# CoProcessor.net
KiCad netlist of a schematic drawn in Altium Designer
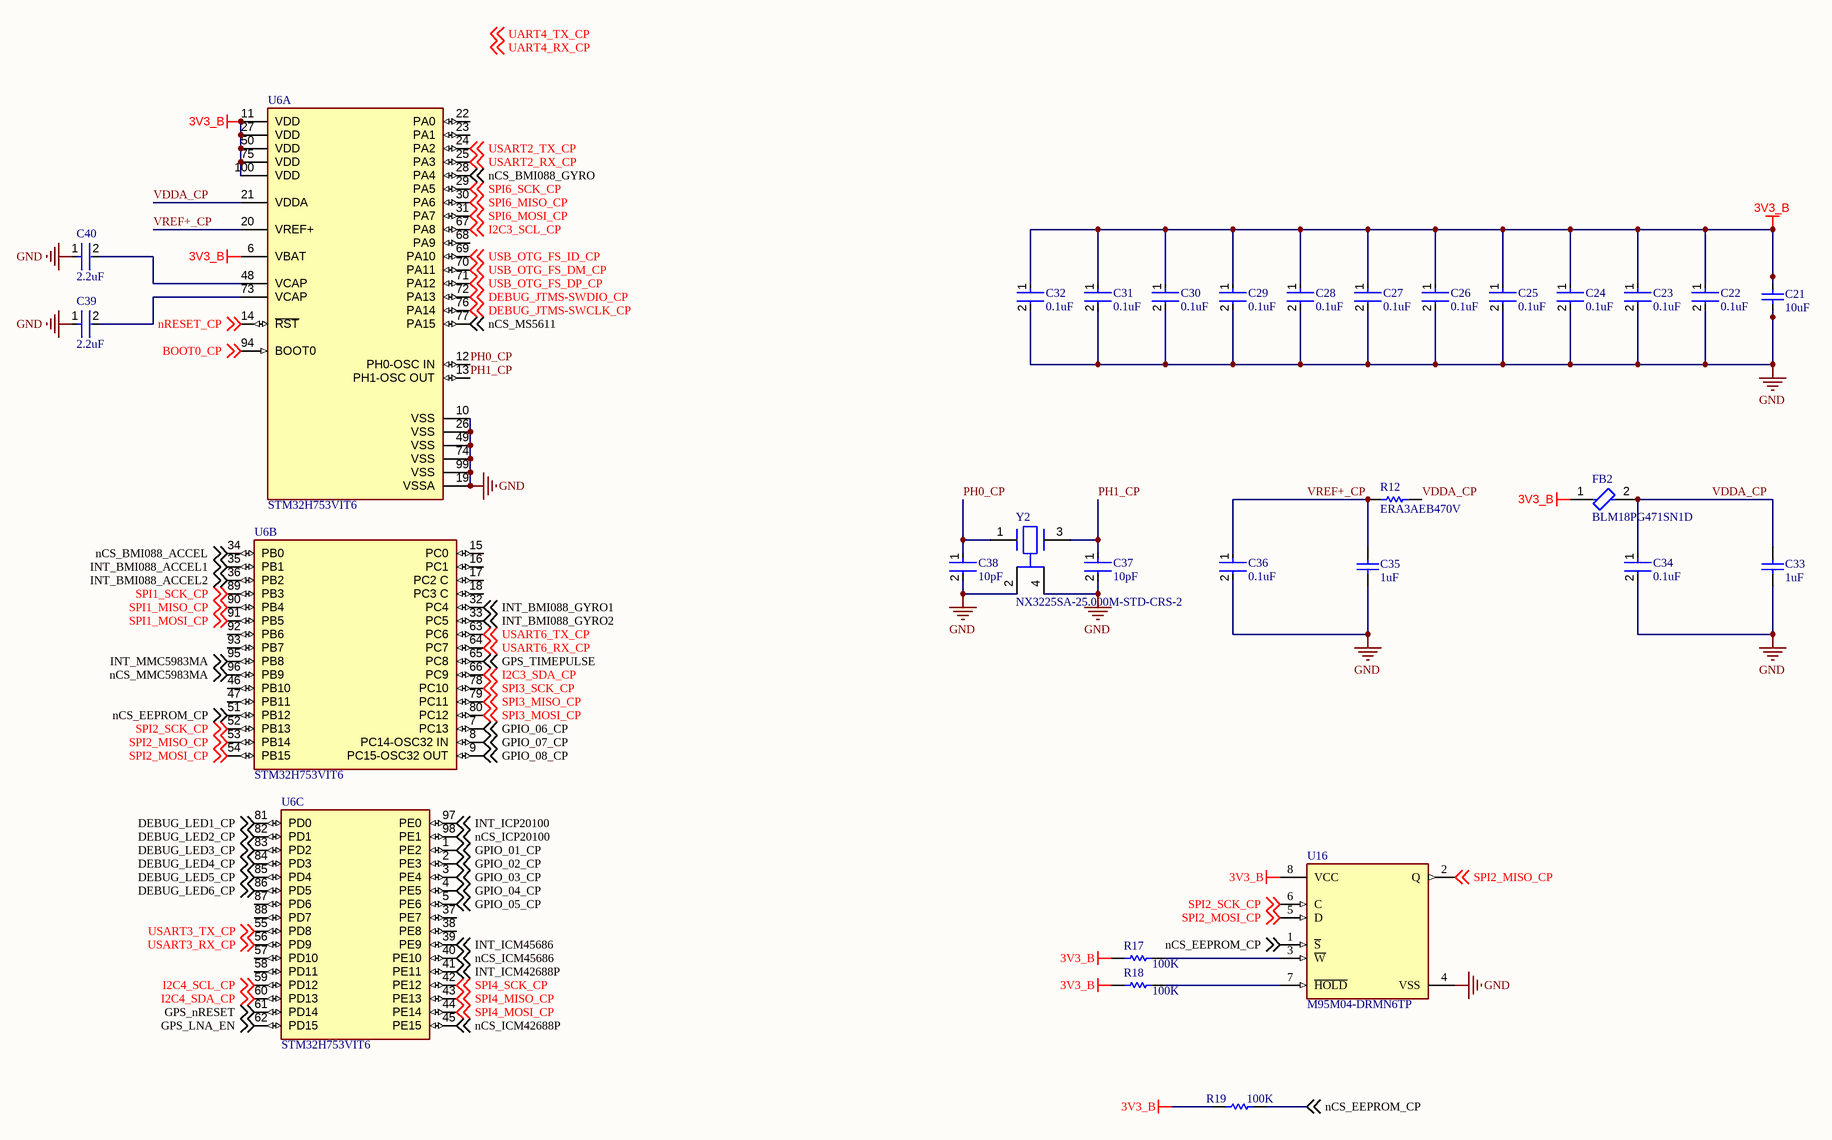
[diagram p0: CoProcessor.SchDoc]

(export (version "E")
  (design (tool "Eeschema 10.0.6"))
  (components
    (comp (ref "C21")
      (value "10uF")
      (footprint "CAPC2013X145X50LL20T25")
      (fields (field (name "MANUFACTURER") "Kemet") (field (name "PART NUMBER") "C0805C106K8RACTU"))
      (libsource (lib "Altium Content Vault") (part "CAP"))
    )
    (comp (ref "C22")
      (value "0.1uF")
      (footprint "FP-C0603C-CF-MFG")
      (description "CAP CER 0.1UF 50V X7R 0603")
      (fields (field (name "TOLERANCE") "0.1") (field (name "MANUFACTURER") "KEMET"))
      (libsource (lib "Altium Content Vault") (part "b4654b650e69147ec39a6b967a45e02"))
    )
    (comp (ref "C23")
      (value "0.1uF")
      (footprint "FP-C0603C-CF-MFG")
      (description "CAP CER 0.1UF 50V X7R 0603")
      (fields (field (name "TOLERANCE") "0.1") (field (name "MANUFACTURER") "KEMET"))
      (libsource (lib "Altium Content Vault") (part "b4654b650e69147ec39a6b967a45e02"))
    )
    (comp (ref "C24")
      (value "0.1uF")
      (footprint "FP-C0603C-CF-MFG")
      (description "CAP CER 0.1UF 50V X7R 0603")
      (fields (field (name "TOLERANCE") "0.1") (field (name "MANUFACTURER") "KEMET"))
      (libsource (lib "Altium Content Vault") (part "b4654b650e69147ec39a6b967a45e02"))
    )
    (comp (ref "C25")
      (value "0.1uF")
      (footprint "FP-C0603C-CF-MFG")
      (description "CAP CER 0.1UF 50V X7R 0603")
      (fields (field (name "TOLERANCE") "0.1") (field (name "MANUFACTURER") "KEMET"))
      (libsource (lib "Altium Content Vault") (part "b4654b650e69147ec39a6b967a45e02"))
    )
    (comp (ref "C26")
      (value "0.1uF")
      (footprint "FP-C0603C-CF-MFG")
      (description "CAP CER 0.1UF 50V X7R 0603")
      (fields (field (name "TOLERANCE") "0.1") (field (name "MANUFACTURER") "KEMET"))
      (libsource (lib "Altium Content Vault") (part "b4654b650e69147ec39a6b967a45e02"))
    )
    (comp (ref "C27")
      (value "0.1uF")
      (footprint "FP-C0603C-CF-MFG")
      (description "CAP CER 0.1UF 50V X7R 0603")
      (fields (field (name "TOLERANCE") "0.1") (field (name "MANUFACTURER") "KEMET"))
      (libsource (lib "Altium Content Vault") (part "b4654b650e69147ec39a6b967a45e02"))
    )
    (comp (ref "C28")
      (value "0.1uF")
      (footprint "FP-C0603C-CF-MFG")
      (description "CAP CER 0.1UF 50V X7R 0603")
      (fields (field (name "TOLERANCE") "0.1") (field (name "MANUFACTURER") "KEMET"))
      (libsource (lib "Altium Content Vault") (part "b4654b650e69147ec39a6b967a45e02"))
    )
    (comp (ref "C29")
      (value "0.1uF")
      (footprint "FP-C0603C-CF-MFG")
      (description "CAP CER 0.1UF 50V X7R 0603")
      (fields (field (name "TOLERANCE") "0.1") (field (name "MANUFACTURER") "KEMET"))
      (libsource (lib "Altium Content Vault") (part "b4654b650e69147ec39a6b967a45e02"))
    )
    (comp (ref "C30")
      (value "0.1uF")
      (footprint "FP-C0603C-CF-MFG")
      (description "CAP CER 0.1UF 50V X7R 0603")
      (fields (field (name "TOLERANCE") "0.1") (field (name "MANUFACTURER") "KEMET"))
      (libsource (lib "Altium Content Vault") (part "b4654b650e69147ec39a6b967a45e02"))
    )
    (comp (ref "C31")
      (value "0.1uF")
      (footprint "FP-C0603C-CF-MFG")
      (description "CAP CER 0.1UF 50V X7R 0603")
      (fields (field (name "TOLERANCE") "0.1") (field (name "MANUFACTURER") "KEMET"))
      (libsource (lib "Altium Content Vault") (part "b4654b650e69147ec39a6b967a45e02"))
    )
    (comp (ref "C32")
      (value "0.1uF")
      (footprint "FP-C0603C-CF-MFG")
      (description "CAP CER 0.1UF 50V X7R 0603")
      (fields (field (name "TOLERANCE") "0.1") (field (name "MANUFACTURER") "KEMET"))
      (libsource (lib "Altium Content Vault") (part "b4654b650e69147ec39a6b967a45e02"))
    )
    (comp (ref "C33")
      (value "1uF")
      (footprint "CAPC1608X90X35LL15T15")
      (fields (field (name "MANUFACTURER") "Kemet") (field (name "PART NUMBER") "C0603C105K4RACTU"))
      (libsource (lib "Altium Content Vault") (part "CAP"))
    )
    (comp (ref "C34")
      (value "0.1uF")
      (footprint "FP-C0603C-CF-MFG")
      (description "CAP CER 0.1UF 50V X7R 0603")
      (fields (field (name "TOLERANCE") "0.1") (field (name "MANUFACTURER") "KEMET"))
      (libsource (lib "Altium Content Vault") (part "b4654b650e69147ec39a6b967a45e02"))
    )
    (comp (ref "C35")
      (value "1uF")
      (footprint "CAPC1608X90X35LL15T15")
      (fields (field (name "MANUFACTURER") "Kemet") (field (name "PART NUMBER") "C0603C105K4RACTU"))
      (libsource (lib "Altium Content Vault") (part "CAP"))
    )
    (comp (ref "C36")
      (value "0.1uF")
      (footprint "FP-C0603C-CF-MFG")
      (description "CAP CER 0.1UF 50V X7R 0603")
      (fields (field (name "TOLERANCE") "0.1") (field (name "MANUFACTURER") "KEMET"))
      (libsource (lib "Altium Content Vault") (part "b4654b650e69147ec39a6b967a45e02"))
    )
    (comp (ref "C37")
      (value "10pF")
      (footprint "FP-C0603C-CF-MFG")
      (description "CAP CER 10PF 50V NP0 0603")
      (fields (field (name "MANUFACTURER") "KEMET") (field (name "TOLERANCE") "0.25 pF"))
      (libsource (lib "Altium Content Vault") (part "b4654b650e69147ec39a6b967a45e02"))
    )
    (comp (ref "C38")
      (value "10pF")
      (footprint "FP-C0603C-CF-MFG")
      (description "CAP CER 10PF 50V NP0 0603")
      (fields (field (name "MANUFACTURER") "KEMET") (field (name "TOLERANCE") "0.25 pF"))
      (libsource (lib "Altium Content Vault") (part "b4654b650e69147ec39a6b967a45e02"))
    )
    (comp (ref "C39")
      (value "2.2uF")
      (footprint "FP-GRM188-0_1-e0_2_0_5-MFG")
      (description "Chip Multilayer Ceramic Capacitors for General Purpose, 0603, 2.2uF, X7R, 15%, 10%, 10V")
      (fields (field (name "VOLTAGE") "10V") (field (name "TOLERANCE") "10%"))
      (libsource (lib "Altium Content Vault") (part "11868f565c42a9108669ba33697ecf6"))
    )
    (comp (ref "C40")
      (value "2.2uF")
      (footprint "FP-GRM188-0_1-e0_2_0_5-MFG")
      (description "Chip Multilayer Ceramic Capacitors for General Purpose, 0603, 2.2uF, X7R, 15%, 10%, 10V")
      (fields (field (name "VOLTAGE") "10V") (field (name "TOLERANCE") "10%"))
      (libsource (lib "Altium Content Vault") (part "11868f565c42a9108669ba33697ecf6"))
    )
    (comp (ref "FB2")
      (value "BLM18PG471SN1D")
      (footprint "FP-BLM18-0_15-t0_8-MFG")
      (description "Chip Ferrite Bead, 0603, 470Ω @ 100MHz, 0.2Ω, 25%, 1A")
      (fields (field (name "TOLERANCE") "25%"))
      (libsource (lib "Altium Content Vault") (part "5f30dd21d616792df468990f7003faa"))
    )
    (comp (ref "R12")
      (value "ERA3AEB470V")
      (footprint "RESC1608X55X30NL20T20")
      (fields (field (name "MANUFACTURER") "Panasonic"))
      (libsource (lib "Altium Content Vault") (part "RES"))
    )
    (comp (ref "R17")
      (value "100K")
      (footprint "RESC1608X55X30ML20T10")
      (fields (field (name "PART NUMBER") "RK73B1JTTD104J") (field (name "MANUFACTURER") "KOA Speer"))
      (libsource (lib "Altium Content Vault") (part "RES"))
    )
    (comp (ref "R18")
      (value "100K")
      (footprint "RESC1608X55X30ML20T10")
      (fields (field (name "PART NUMBER") "RK73B1JTTD104J") (field (name "MANUFACTURER") "KOA Speer"))
      (libsource (lib "Altium Content Vault") (part "RES"))
    )
    (comp (ref "R19")
      (value "100K")
      (footprint "RESC1608X55X30ML20T10")
      (fields (field (name "PART NUMBER") "RK73B1JTTD104J") (field (name "MANUFACTURER") "KOA Speer"))
      (libsource (lib "Altium Content Vault") (part "RES"))
    )
    (comp (ref "U6")
      (value "STM32H753VIT6")
      (footprint "FP-LQFP100-1L-MFG")
      (description "LQFP 100 14X14X1.4")
      (fields
        (field (name "OCTOPART") "https://octopart.com/stm32h753vit6-stmicroelectronics-87879769")
        (field (name "MANUFACTURER") "STMicroelectronics")
      )
      (libsource (lib "Altium Content Vault") (part "0d804454ec25a714beb1806164230ed"))
    )
    (comp (ref "U16")
      (value "M95M04-DRMN6TP")
      (footprint "FP-SO8N-SO-A-IPC_C")
      (description "STANDARD SERIAL EEPROM")
      (libsource (lib "Altium Content Vault") (part "c55af301368cfa6937ebbf8cb00c05d"))
    )
    (comp (ref "Y2")
      (value "NX3225SA-25.000M-STD-CRS-2")
      (footprint "FP-NX3225SA-MFG")
      (description "CRYSTAL 25.0000MHZ 8PF SMD")
      (fields
        (field (name "OCTOPART") "https://octopart.com/nx3225sa-25.000m-std-crs-2-ndk-51374293")
        (field (name "MANUFACTURER") "NDK")
      )
      (libsource (lib "Altium Content Vault") (part "2e6e5a9c86ccbddb5e6335a7c0ff6ff"))
    )
  )
  (nets
    (net (code "1") (name "/PH0_CP") (class "Default")
      (node (ref "C38") (pin "1") (pinfunction "1_1") (pintype "passive"))
      (node (ref "U6") (pin "12") (pinfunction "PH0-OSC_IN_12") (pintype "bidirectional"))
      (node (ref "Y2") (pin "1") (pinfunction "1_1") (pintype "passive"))
    )
    (net (code "2") (name "/PH1_CP") (class "Default")
      (node (ref "C37") (pin "1") (pinfunction "1_1") (pintype "passive"))
      (node (ref "U6") (pin "13") (pinfunction "PH1-OSC_OUT_13") (pintype "bidirectional"))
      (node (ref "Y2") (pin "3") (pinfunction "3_3") (pintype "passive"))
    )
    (net (code "3") (name "/VDDA_CP") (class "Default")
      (node (ref "C33") (pin "1") (pinfunction "1_1") (pintype "passive"))
      (node (ref "C34") (pin "1") (pinfunction "1_1") (pintype "passive"))
      (node (ref "FB2") (pin "2") (pinfunction "2_2") (pintype "passive"))
      (node (ref "R12") (pin "2") (pinfunction "2_2") (pintype "passive"))
      (node (ref "U6") (pin "21") (pinfunction "VDDA_21") (pintype "power_in"))
    )
    (net (code "4") (name "/VREF+_CP") (class "Default")
      (node (ref "C35") (pin "1") (pinfunction "1_1") (pintype "passive"))
      (node (ref "C36") (pin "1") (pinfunction "1_1") (pintype "passive"))
      (node (ref "R12") (pin "1") (pinfunction "1_1") (pintype "passive"))
      (node (ref "U6") (pin "20") (pinfunction "VREF+_20") (pintype "power_in"))
    )
    (net (code "5") (name "3V3_B") (class "Default")
      (node (ref "C21") (pin "1") (pinfunction "1_1") (pintype "passive"))
      (node (ref "C22") (pin "1") (pinfunction "1_1") (pintype "passive"))
      (node (ref "C23") (pin "1") (pinfunction "1_1") (pintype "passive"))
      (node (ref "C24") (pin "1") (pinfunction "1_1") (pintype "passive"))
      (node (ref "C25") (pin "1") (pinfunction "1_1") (pintype "passive"))
      (node (ref "C26") (pin "1") (pinfunction "1_1") (pintype "passive"))
      (node (ref "C27") (pin "1") (pinfunction "1_1") (pintype "passive"))
      (node (ref "C28") (pin "1") (pinfunction "1_1") (pintype "passive"))
      (node (ref "C29") (pin "1") (pinfunction "1_1") (pintype "passive"))
      (node (ref "C30") (pin "1") (pinfunction "1_1") (pintype "passive"))
      (node (ref "C31") (pin "1") (pinfunction "1_1") (pintype "passive"))
      (node (ref "C32") (pin "1") (pinfunction "1_1") (pintype "passive"))
      (node (ref "FB2") (pin "1") (pinfunction "1_1") (pintype "passive"))
      (node (ref "R17") (pin "2") (pinfunction "2_2") (pintype "passive"))
      (node (ref "R18") (pin "2") (pinfunction "2_2") (pintype "passive"))
      (node (ref "R19") (pin "2") (pinfunction "2_2") (pintype "passive"))
      (node (ref "U16") (pin "8") (pinfunction "VCC_8") (pintype "power_in"))
      (node (ref "U6") (pin "100") (pinfunction "VDD_100") (pintype "power_in"))
      (node (ref "U6") (pin "11") (pinfunction "VDD_11") (pintype "power_in"))
      (node (ref "U6") (pin "27") (pinfunction "VDD_27") (pintype "power_in"))
      (node (ref "U6") (pin "50") (pinfunction "VDD_50") (pintype "power_in"))
      (node (ref "U6") (pin "6") (pinfunction "VBAT_6") (pintype "power_in"))
      (node (ref "U6") (pin "75") (pinfunction "VDD_75") (pintype "power_in"))
    )
    (net (code "6") (name "BOOT0_CP") (class "Default")
      (node (ref "U6") (pin "94") (pinfunction "BOOT0_94") (pintype "input"))
    )
    (net (code "7") (name "DEBUG_JTMS-SWCLK_CP") (class "Default")
      (node (ref "U6") (pin "76") (pinfunction "PA14_76") (pintype "bidirectional"))
    )
    (net (code "8") (name "DEBUG_JTMS-SWDIO_CP") (class "Default")
      (node (ref "U6") (pin "72") (pinfunction "PA13_72") (pintype "bidirectional"))
    )
    (net (code "9") (name "DEBUG_LED1_CP") (class "Default")
      (node (ref "U6") (pin "81") (pinfunction "PD0_81") (pintype "bidirectional"))
    )
    (net (code "10") (name "DEBUG_LED2_CP") (class "Default")
      (node (ref "U6") (pin "82") (pinfunction "PD1_82") (pintype "bidirectional"))
    )
    (net (code "11") (name "DEBUG_LED3_CP") (class "Default")
      (node (ref "U6") (pin "83") (pinfunction "PD2_83") (pintype "bidirectional"))
    )
    (net (code "12") (name "DEBUG_LED4_CP") (class "Default")
      (node (ref "U6") (pin "84") (pinfunction "PD3_84") (pintype "bidirectional"))
    )
    (net (code "13") (name "DEBUG_LED5_CP") (class "Default")
      (node (ref "U6") (pin "85") (pinfunction "PD4_85") (pintype "bidirectional"))
    )
    (net (code "14") (name "DEBUG_LED6_CP") (class "Default")
      (node (ref "U6") (pin "86") (pinfunction "PD5_86") (pintype "bidirectional"))
    )
    (net (code "15") (name "GND") (class "Default")
      (node (ref "C21") (pin "2") (pinfunction "2_2") (pintype "passive"))
      (node (ref "C22") (pin "2") (pinfunction "2_2") (pintype "passive"))
      (node (ref "C23") (pin "2") (pinfunction "2_2") (pintype "passive"))
      (node (ref "C24") (pin "2") (pinfunction "2_2") (pintype "passive"))
      (node (ref "C25") (pin "2") (pinfunction "2_2") (pintype "passive"))
      (node (ref "C26") (pin "2") (pinfunction "2_2") (pintype "passive"))
      (node (ref "C27") (pin "2") (pinfunction "2_2") (pintype "passive"))
      (node (ref "C28") (pin "2") (pinfunction "2_2") (pintype "passive"))
      (node (ref "C29") (pin "2") (pinfunction "2_2") (pintype "passive"))
      (node (ref "C30") (pin "2") (pinfunction "2_2") (pintype "passive"))
      (node (ref "C31") (pin "2") (pinfunction "2_2") (pintype "passive"))
      (node (ref "C32") (pin "2") (pinfunction "2_2") (pintype "passive"))
      (node (ref "C33") (pin "2") (pinfunction "2_2") (pintype "passive"))
      (node (ref "C34") (pin "2") (pinfunction "2_2") (pintype "passive"))
      (node (ref "C35") (pin "2") (pinfunction "2_2") (pintype "passive"))
      (node (ref "C36") (pin "2") (pinfunction "2_2") (pintype "passive"))
      (node (ref "C37") (pin "2") (pinfunction "2_2") (pintype "passive"))
      (node (ref "C38") (pin "2") (pinfunction "2_2") (pintype "passive"))
      (node (ref "C39") (pin "1") (pinfunction "1_1") (pintype "passive"))
      (node (ref "C40") (pin "1") (pinfunction "1_1") (pintype "passive"))
      (node (ref "U16") (pin "4") (pinfunction "VSS_4") (pintype "power_in"))
      (node (ref "U6") (pin "10") (pinfunction "VSS_10") (pintype "power_in"))
      (node (ref "U6") (pin "19") (pinfunction "VSSA_19") (pintype "power_in"))
      (node (ref "U6") (pin "26") (pinfunction "VSS_26") (pintype "power_in"))
      (node (ref "U6") (pin "49") (pinfunction "VSS_49") (pintype "power_in"))
      (node (ref "U6") (pin "74") (pinfunction "VSS_74") (pintype "power_in"))
      (node (ref "U6") (pin "99") (pinfunction "VSS_99") (pintype "power_in"))
      (node (ref "Y2") (pin "2") (pinfunction "GND_2") (pintype "power_in"))
      (node (ref "Y2") (pin "4") (pinfunction "GND_4") (pintype "power_in"))
    )
    (net (code "16") (name "GPIO_01_CP") (class "Default")
      (node (ref "U6") (pin "1") (pinfunction "PE2_1") (pintype "bidirectional"))
    )
    (net (code "17") (name "GPIO_02_CP") (class "Default")
      (node (ref "U6") (pin "2") (pinfunction "PE3_2") (pintype "bidirectional"))
    )
    (net (code "18") (name "GPIO_03_CP") (class "Default")
      (node (ref "U6") (pin "3") (pinfunction "PE4_3") (pintype "bidirectional"))
    )
    (net (code "19") (name "GPIO_04_CP") (class "Default")
      (node (ref "U6") (pin "4") (pinfunction "PE5_4") (pintype "bidirectional"))
    )
    (net (code "20") (name "GPIO_05_CP") (class "Default")
      (node (ref "U6") (pin "5") (pinfunction "PE6_5") (pintype "bidirectional"))
    )
    (net (code "21") (name "GPIO_06_CP") (class "Default")
      (node (ref "U6") (pin "7") (pinfunction "PC13_7") (pintype "bidirectional"))
    )
    (net (code "22") (name "GPIO_07_CP") (class "Default")
      (node (ref "U6") (pin "8") (pinfunction "PC14-OSC32_IN_8") (pintype "bidirectional"))
    )
    (net (code "23") (name "GPIO_08_CP") (class "Default")
      (node (ref "U6") (pin "9") (pinfunction "PC15-OSC32_OUT_9") (pintype "bidirectional"))
    )
    (net (code "24") (name "GPS_LNA_EN") (class "Default")
      (node (ref "U6") (pin "62") (pinfunction "PD15_62") (pintype "bidirectional"))
    )
    (net (code "25") (name "GPS_TIMEPULSE") (class "Default")
      (node (ref "U6") (pin "65") (pinfunction "PC8_65") (pintype "bidirectional"))
    )
    (net (code "26") (name "GPS_nRESET") (class "Default")
      (node (ref "U6") (pin "61") (pinfunction "PD14_61") (pintype "bidirectional"))
    )
    (net (code "27") (name "I2C3_SCL_CP") (class "Default")
      (node (ref "U6") (pin "67") (pinfunction "PA8_67") (pintype "bidirectional"))
    )
    (net (code "28") (name "I2C3_SDA_CP") (class "Default")
      (node (ref "U6") (pin "66") (pinfunction "PC9_66") (pintype "bidirectional"))
    )
    (net (code "29") (name "I2C4_SCL_CP") (class "Default")
      (node (ref "U6") (pin "59") (pinfunction "PD12_59") (pintype "bidirectional"))
    )
    (net (code "30") (name "I2C4_SDA_CP") (class "Default")
      (node (ref "U6") (pin "60") (pinfunction "PD13_60") (pintype "bidirectional"))
    )
    (net (code "31") (name "INT_BMI088_ACCEL1") (class "Default")
      (node (ref "U6") (pin "35") (pinfunction "PB1_35") (pintype "bidirectional"))
    )
    (net (code "32") (name "INT_BMI088_ACCEL2") (class "Default")
      (node (ref "U6") (pin "36") (pinfunction "PB2_36") (pintype "bidirectional"))
    )
    (net (code "33") (name "INT_BMI088_GYRO1") (class "Default")
      (node (ref "U6") (pin "32") (pinfunction "PC4_32") (pintype "bidirectional"))
    )
    (net (code "34") (name "INT_BMI088_GYRO2") (class "Default")
      (node (ref "U6") (pin "33") (pinfunction "PC5_33") (pintype "bidirectional"))
    )
    (net (code "35") (name "INT_ICM42688P") (class "Default")
      (node (ref "U6") (pin "41") (pinfunction "PE11_41") (pintype "bidirectional"))
    )
    (net (code "36") (name "INT_ICM45686") (class "Default")
      (node (ref "U6") (pin "39") (pinfunction "PE9_39") (pintype "bidirectional"))
    )
    (net (code "37") (name "INT_ICP20100") (class "Default")
      (node (ref "U6") (pin "97") (pinfunction "PE0_97") (pintype "bidirectional"))
    )
    (net (code "38") (name "INT_MMC5983MA") (class "Default")
      (node (ref "U6") (pin "95") (pinfunction "PB8_95") (pintype "bidirectional"))
    )
    (net (code "39") (name "Net-(C39-Pad2)") (class "Default")
      (node (ref "C39") (pin "2") (pinfunction "2_2") (pintype "passive"))
      (node (ref "U6") (pin "73") (pinfunction "VCAP_73") (pintype "power_in"))
    )
    (net (code "40") (name "Net-(C40-Pad2)") (class "Default")
      (node (ref "C40") (pin "2") (pinfunction "2_2") (pintype "passive"))
      (node (ref "U6") (pin "48") (pinfunction "VCAP_48") (pintype "power_in"))
    )
    (net (code "41") (name "Net-(U16-~{HOLD})") (class "Default")
      (node (ref "R18") (pin "1") (pinfunction "1_1") (pintype "passive"))
      (node (ref "U16") (pin "7") (pinfunction "~{HOLD}_7") (pintype "input"))
    )
    (net (code "42") (name "Net-(U16-~{W})") (class "Default")
      (node (ref "R17") (pin "1") (pinfunction "1_1") (pintype "passive"))
      (node (ref "U16") (pin "3") (pinfunction "~{W}_3") (pintype "input"))
    )
    (net (code "43") (name "SPI1_MISO_CP") (class "Default")
      (node (ref "U6") (pin "90") (pinfunction "PB4_90") (pintype "bidirectional"))
    )
    (net (code "44") (name "SPI1_MOSI_CP") (class "Default")
      (node (ref "U6") (pin "91") (pinfunction "PB5_91") (pintype "bidirectional"))
    )
    (net (code "45") (name "SPI1_SCK_CP") (class "Default")
      (node (ref "U6") (pin "89") (pinfunction "PB3_89") (pintype "bidirectional"))
    )
    (net (code "46") (name "SPI2_MISO_CP") (class "Default")
      (node (ref "U16") (pin "2") (pinfunction "Q_2") (pintype "output"))
      (node (ref "U6") (pin "53") (pinfunction "PB14_53") (pintype "bidirectional"))
    )
    (net (code "47") (name "SPI2_MOSI_CP") (class "Default")
      (node (ref "U16") (pin "5") (pinfunction "D_5") (pintype "input"))
      (node (ref "U6") (pin "54") (pinfunction "PB15_54") (pintype "bidirectional"))
    )
    (net (code "48") (name "SPI2_SCK_CP") (class "Default")
      (node (ref "U16") (pin "6") (pinfunction "C_6") (pintype "input"))
      (node (ref "U6") (pin "52") (pinfunction "PB13_52") (pintype "bidirectional"))
    )
    (net (code "49") (name "SPI3_MISO_CP") (class "Default")
      (node (ref "U6") (pin "79") (pinfunction "PC11_79") (pintype "bidirectional"))
    )
    (net (code "50") (name "SPI3_MOSI_CP") (class "Default")
      (node (ref "U6") (pin "80") (pinfunction "PC12_80") (pintype "bidirectional"))
    )
    (net (code "51") (name "SPI3_SCK_CP") (class "Default")
      (node (ref "U6") (pin "78") (pinfunction "PC10_78") (pintype "bidirectional"))
    )
    (net (code "52") (name "SPI4_MISO_CP") (class "Default")
      (node (ref "U6") (pin "43") (pinfunction "PE13_43") (pintype "bidirectional"))
    )
    (net (code "53") (name "SPI4_MOSI_CP") (class "Default")
      (node (ref "U6") (pin "44") (pinfunction "PE14_44") (pintype "bidirectional"))
    )
    (net (code "54") (name "SPI4_SCK_CP") (class "Default")
      (node (ref "U6") (pin "42") (pinfunction "PE12_42") (pintype "bidirectional"))
    )
    (net (code "55") (name "SPI6_MISO_CP") (class "Default")
      (node (ref "U6") (pin "30") (pinfunction "PA6_30") (pintype "bidirectional"))
    )
    (net (code "56") (name "SPI6_MOSI_CP") (class "Default")
      (node (ref "U6") (pin "31") (pinfunction "PA7_31") (pintype "bidirectional"))
    )
    (net (code "57") (name "SPI6_SCK_CP") (class "Default")
      (node (ref "U6") (pin "29") (pinfunction "PA5_29") (pintype "bidirectional"))
    )
    (net (code "60") (name "USART2_RX_CP") (class "Default")
      (node (ref "U6") (pin "25") (pinfunction "PA3_25") (pintype "bidirectional"))
    )
    (net (code "61") (name "USART2_TX_CP") (class "Default")
      (node (ref "U6") (pin "24") (pinfunction "PA2_24") (pintype "bidirectional"))
    )
    (net (code "62") (name "USART3_RX_CP") (class "Default")
      (node (ref "U6") (pin "56") (pinfunction "PD9_56") (pintype "bidirectional"))
    )
    (net (code "63") (name "USART3_TX_CP") (class "Default")
      (node (ref "U6") (pin "55") (pinfunction "PD8_55") (pintype "bidirectional"))
    )
    (net (code "64") (name "USART6_RX_CP") (class "Default")
      (node (ref "U6") (pin "64") (pinfunction "PC7_64") (pintype "bidirectional"))
    )
    (net (code "65") (name "USART6_TX_CP") (class "Default")
      (node (ref "U6") (pin "63") (pinfunction "PC6_63") (pintype "bidirectional"))
    )
    (net (code "66") (name "USB_OTG_FS_DM_CP") (class "Default")
      (node (ref "U6") (pin "70") (pinfunction "PA11_70") (pintype "bidirectional"))
    )
    (net (code "67") (name "USB_OTG_FS_DP_CP") (class "Default")
      (node (ref "U6") (pin "71") (pinfunction "PA12_71") (pintype "bidirectional"))
    )
    (net (code "68") (name "USB_OTG_FS_ID_CP") (class "Default")
      (node (ref "U6") (pin "69") (pinfunction "PA10_69") (pintype "bidirectional"))
    )
    (net (code "69") (name "nCS_BMI088_ACCEL") (class "Default")
      (node (ref "U6") (pin "34") (pinfunction "PB0_34") (pintype "bidirectional"))
    )
    (net (code "70") (name "nCS_BMI088_GYRO") (class "Default")
      (node (ref "U6") (pin "28") (pinfunction "PA4_28") (pintype "bidirectional"))
    )
    (net (code "71") (name "nCS_EEPROM_CP") (class "Default")
      (node (ref "R19") (pin "1") (pinfunction "1_1") (pintype "passive"))
      (node (ref "U16") (pin "1") (pinfunction "~{S}_1") (pintype "input"))
      (node (ref "U6") (pin "51") (pinfunction "PB12_51") (pintype "bidirectional"))
    )
    (net (code "72") (name "nCS_ICM42688P") (class "Default")
      (node (ref "U6") (pin "45") (pinfunction "PE15_45") (pintype "bidirectional"))
    )
    (net (code "73") (name "nCS_ICM45686") (class "Default")
      (node (ref "U6") (pin "40") (pinfunction "PE10_40") (pintype "bidirectional"))
    )
    (net (code "74") (name "nCS_ICP20100") (class "Default")
      (node (ref "U6") (pin "98") (pinfunction "PE1_98") (pintype "bidirectional"))
    )
    (net (code "75") (name "nCS_MMC5983MA") (class "Default")
      (node (ref "U6") (pin "96") (pinfunction "PB9_96") (pintype "bidirectional"))
    )
    (net (code "76") (name "nCS_MS5611") (class "Default")
      (node (ref "U6") (pin "77") (pinfunction "PA15_77") (pintype "bidirectional"))
    )
    (net (code "77") (name "nRESET_CP") (class "Default")
      (node (ref "U6") (pin "14") (pinfunction "~{RST}_14") (pintype "bidirectional"))
    )
    (net (code "78") (name "unconnected-(U6A-PA0-Pad22)") (class "Default")
      (node (ref "U6") (pin "22") (pinfunction "PA0_22") (pintype "bidirectional"))
    )
    (net (code "79") (name "unconnected-(U6A-PA1-Pad23)") (class "Default")
      (node (ref "U6") (pin "23") (pinfunction "PA1_23") (pintype "bidirectional"))
    )
    (net (code "80") (name "unconnected-(U6A-PA9-Pad68)") (class "Default")
      (node (ref "U6") (pin "68") (pinfunction "PA9_68") (pintype "bidirectional"))
    )
    (net (code "81") (name "unconnected-(U6B-PB6-Pad92)") (class "Default")
      (node (ref "U6") (pin "92") (pinfunction "PB6_92") (pintype "bidirectional"))
    )
    (net (code "82") (name "unconnected-(U6B-PB7-Pad93)") (class "Default")
      (node (ref "U6") (pin "93") (pinfunction "PB7_93") (pintype "bidirectional"))
    )
    (net (code "83") (name "unconnected-(U6B-PB10-Pad46)") (class "Default")
      (node (ref "U6") (pin "46") (pinfunction "PB10_46") (pintype "bidirectional"))
    )
    (net (code "84") (name "unconnected-(U6B-PB11-Pad47)") (class "Default")
      (node (ref "U6") (pin "47") (pinfunction "PB11_47") (pintype "bidirectional"))
    )
    (net (code "85") (name "unconnected-(U6B-PC0-Pad15)") (class "Default")
      (node (ref "U6") (pin "15") (pinfunction "PC0_15") (pintype "bidirectional"))
    )
    (net (code "86") (name "unconnected-(U6B-PC1-Pad16)") (class "Default")
      (node (ref "U6") (pin "16") (pinfunction "PC1_16") (pintype "bidirectional"))
    )
    (net (code "87") (name "unconnected-(U6B-PC2_C-Pad17)") (class "Default")
      (node (ref "U6") (pin "17") (pinfunction "PC2_C_17") (pintype "bidirectional"))
    )
    (net (code "88") (name "unconnected-(U6B-PC3_C-Pad18)") (class "Default")
      (node (ref "U6") (pin "18") (pinfunction "PC3_C_18") (pintype "bidirectional"))
    )
    (net (code "89") (name "unconnected-(U6C-PD6-Pad87)") (class "Default")
      (node (ref "U6") (pin "87") (pinfunction "PD6_87") (pintype "bidirectional"))
    )
    (net (code "90") (name "unconnected-(U6C-PD7-Pad88)") (class "Default")
      (node (ref "U6") (pin "88") (pinfunction "PD7_88") (pintype "bidirectional"))
    )
    (net (code "91") (name "unconnected-(U6C-PD10-Pad57)") (class "Default")
      (node (ref "U6") (pin "57") (pinfunction "PD10_57") (pintype "bidirectional"))
    )
    (net (code "92") (name "unconnected-(U6C-PD11-Pad58)") (class "Default")
      (node (ref "U6") (pin "58") (pinfunction "PD11_58") (pintype "bidirectional"))
    )
    (net (code "93") (name "unconnected-(U6C-PE7-Pad37)") (class "Default")
      (node (ref "U6") (pin "37") (pinfunction "PE7_37") (pintype "bidirectional"))
    )
    (net (code "94") (name "unconnected-(U6C-PE8-Pad38)") (class "Default")
      (node (ref "U6") (pin "38") (pinfunction "PE8_38") (pintype "bidirectional"))
    )
  )
)
